# db9neogeo.net
KiCad netlist of a schematic drawn in EAGLE
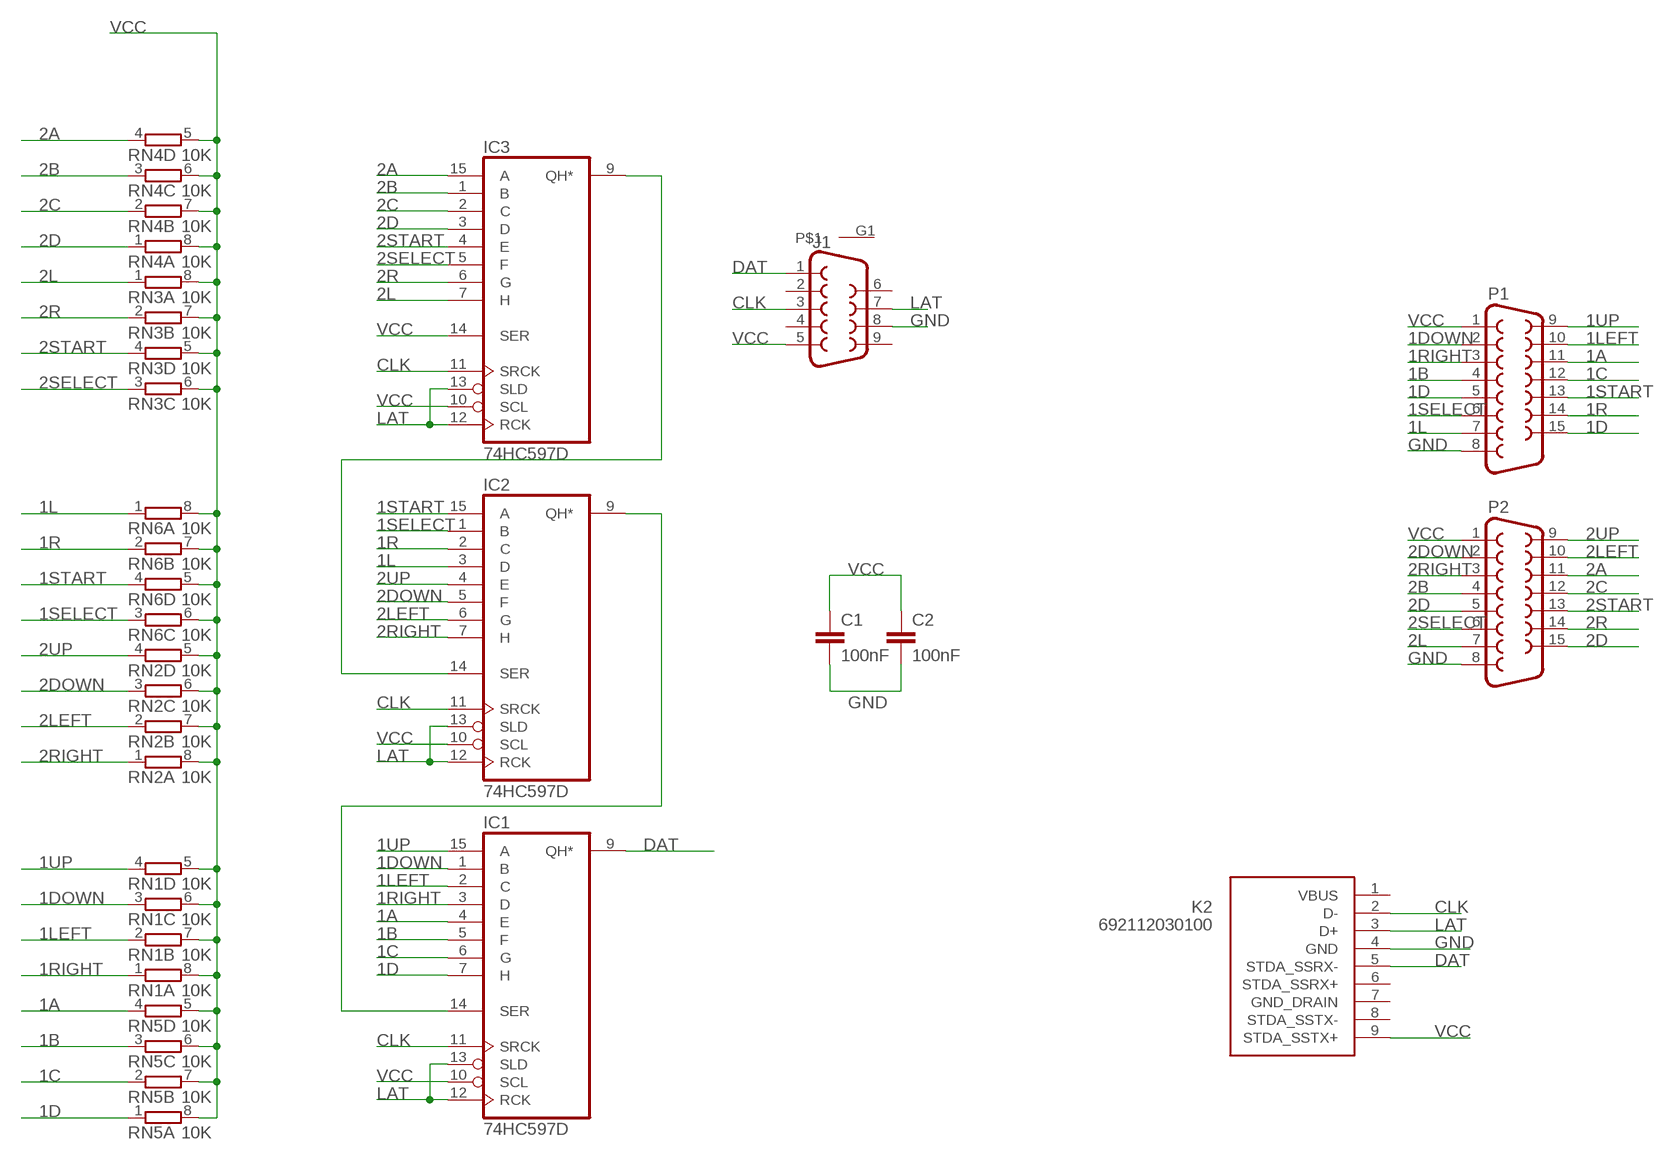
[diagram p0: schematic, sheet 1]

(export (version "E")
  (design (tool "Eeschema 10.0.6"))
  (components
    (comp (ref "C1")
      (value "100nF")
      (footprint "eagle-import:C0603K")
      (libsource (lib "eagle-import") (part "C-EUC0603K"))
    )
    (comp (ref "C2")
      (value "100nF")
      (footprint "eagle-import:C0603K")
      (libsource (lib "eagle-import") (part "C-EUC0603K"))
    )
    (comp (ref "IC1")
      (value "74HC597D")
      (footprint "eagle-import:SO16")
      (libsource (lib "eagle-import") (part "74597DHC"))
    )
    (comp (ref "IC2")
      (value "74HC597D")
      (footprint "eagle-import:SO16")
      (libsource (lib "eagle-import") (part "74597DHC"))
    )
    (comp (ref "IC3")
      (value "74HC597D")
      (footprint "eagle-import:SO16")
      (libsource (lib "eagle-import") (part "74597DHC"))
    )
    (comp (ref "J1")
      (value "DB9FEMALE")
      (footprint "eagle-import:DB9")
      (libsource (lib "eagle-import") (part "DB9FEMALE"))
    )
    (comp (ref "K2")
      (value "692112030100")
      (footprint "eagle-import:692112030100")
      (libsource (lib "eagle-import") (part "692112030100"))
    )
    (comp (ref "P1")
      (value "F15HP")
      (footprint "eagle-import:F15HP")
      (libsource (lib "eagle-import") (part "F15HP"))
    )
    (comp (ref "P2")
      (value "F15HP")
      (footprint "eagle-import:F15HP")
      (libsource (lib "eagle-import") (part "F15HP"))
    )
    (comp (ref "RN1")
      (value "10K")
      (footprint "eagle-import:0603-ARC")
      (libsource (lib "eagle-import") (part "4R-N0603-ARC"))
    )
    (comp (ref "RN2")
      (value "10K")
      (footprint "eagle-import:0603-ARC")
      (libsource (lib "eagle-import") (part "4R-N0603-ARC"))
    )
    (comp (ref "RN3")
      (value "10K")
      (footprint "eagle-import:0603-ARC")
      (libsource (lib "eagle-import") (part "4R-N0603-ARC"))
    )
    (comp (ref "RN4")
      (value "10K")
      (footprint "eagle-import:0603-ARC")
      (libsource (lib "eagle-import") (part "4R-N0603-ARC"))
    )
    (comp (ref "RN5")
      (value "10K")
      (footprint "eagle-import:0603-ARC")
      (libsource (lib "eagle-import") (part "4R-N0603-ARC"))
    )
    (comp (ref "RN6")
      (value "10K")
      (footprint "eagle-import:0603-ARC")
      (libsource (lib "eagle-import") (part "4R-N0603-ARC"))
    )
  )
  (nets
    (net (code "1") (name "/1A") (class "Default")
      (node (ref "IC1") (pin "4") (pinfunction "E_4") (pintype "input"))
      (node (ref "P1") (pin "11") (pinfunction "11_11") (pintype "passive"))
      (node (ref "RN5") (pin "4") (pinfunction "1_4") (pintype "passive"))
    )
    (net (code "2") (name "/1B") (class "Default")
      (node (ref "IC1") (pin "5") (pinfunction "F_5") (pintype "input"))
      (node (ref "P1") (pin "4") (pinfunction "4_4") (pintype "passive"))
      (node (ref "RN5") (pin "3") (pinfunction "1_3") (pintype "passive"))
    )
    (net (code "3") (name "/1C") (class "Default")
      (node (ref "IC1") (pin "6") (pinfunction "G_6") (pintype "input"))
      (node (ref "P1") (pin "12") (pinfunction "12_12") (pintype "passive"))
      (node (ref "RN5") (pin "2") (pinfunction "1_2") (pintype "passive"))
    )
    (net (code "4") (name "/1D") (class "Default")
      (node (ref "IC1") (pin "7") (pinfunction "H_7") (pintype "input"))
      (node (ref "P1") (pin "15") (pinfunction "15_15") (pintype "passive"))
      (node (ref "P1") (pin "5") (pinfunction "5_5") (pintype "passive"))
      (node (ref "RN5") (pin "1") (pinfunction "1_1") (pintype "passive"))
    )
    (net (code "5") (name "/1DOWN") (class "Default")
      (node (ref "IC1") (pin "1") (pinfunction "B_1") (pintype "input"))
      (node (ref "P1") (pin "2") (pinfunction "2_2") (pintype "passive"))
      (node (ref "RN1") (pin "3") (pinfunction "1_3") (pintype "passive"))
    )
    (net (code "6") (name "/1L") (class "Default")
      (node (ref "IC2") (pin "3") (pinfunction "D_3") (pintype "input"))
      (node (ref "P1") (pin "7") (pinfunction "7_7") (pintype "passive"))
      (node (ref "RN6") (pin "1") (pinfunction "1_1") (pintype "passive"))
    )
    (net (code "7") (name "/1LEFT") (class "Default")
      (node (ref "IC1") (pin "2") (pinfunction "C_2") (pintype "input"))
      (node (ref "P1") (pin "10") (pinfunction "10_10") (pintype "passive"))
      (node (ref "RN1") (pin "2") (pinfunction "1_2") (pintype "passive"))
    )
    (net (code "8") (name "/1R") (class "Default")
      (node (ref "IC2") (pin "2") (pinfunction "C_2") (pintype "input"))
      (node (ref "P1") (pin "14") (pinfunction "14_14") (pintype "passive"))
      (node (ref "RN6") (pin "2") (pinfunction "1_2") (pintype "passive"))
    )
    (net (code "9") (name "/1RIGHT") (class "Default")
      (node (ref "IC1") (pin "3") (pinfunction "D_3") (pintype "input"))
      (node (ref "P1") (pin "3") (pinfunction "3_3") (pintype "passive"))
      (node (ref "RN1") (pin "1") (pinfunction "1_1") (pintype "passive"))
    )
    (net (code "10") (name "/1SELECT") (class "Default")
      (node (ref "IC2") (pin "1") (pinfunction "B_1") (pintype "input"))
      (node (ref "P1") (pin "6") (pinfunction "6_6") (pintype "passive"))
      (node (ref "RN6") (pin "3") (pinfunction "1_3") (pintype "passive"))
    )
    (net (code "11") (name "/1START") (class "Default")
      (node (ref "IC2") (pin "15") (pinfunction "A_15") (pintype "input"))
      (node (ref "P1") (pin "13") (pinfunction "13_13") (pintype "passive"))
      (node (ref "RN6") (pin "4") (pinfunction "1_4") (pintype "passive"))
    )
    (net (code "12") (name "/1UP") (class "Default")
      (node (ref "IC1") (pin "15") (pinfunction "A_15") (pintype "input"))
      (node (ref "P1") (pin "9") (pinfunction "9_9") (pintype "passive"))
      (node (ref "RN1") (pin "4") (pinfunction "1_4") (pintype "passive"))
    )
    (net (code "13") (name "/2A") (class "Default")
      (node (ref "IC3") (pin "15") (pinfunction "A_15") (pintype "input"))
      (node (ref "P2") (pin "11") (pinfunction "11_11") (pintype "passive"))
      (node (ref "RN4") (pin "4") (pinfunction "1_4") (pintype "passive"))
    )
    (net (code "14") (name "/2B") (class "Default")
      (node (ref "IC3") (pin "1") (pinfunction "B_1") (pintype "input"))
      (node (ref "P2") (pin "4") (pinfunction "4_4") (pintype "passive"))
      (node (ref "RN4") (pin "3") (pinfunction "1_3") (pintype "passive"))
    )
    (net (code "15") (name "/2C") (class "Default")
      (node (ref "IC3") (pin "2") (pinfunction "C_2") (pintype "input"))
      (node (ref "P2") (pin "12") (pinfunction "12_12") (pintype "passive"))
      (node (ref "RN4") (pin "2") (pinfunction "1_2") (pintype "passive"))
    )
    (net (code "16") (name "/2D") (class "Default")
      (node (ref "IC3") (pin "3") (pinfunction "D_3") (pintype "input"))
      (node (ref "P2") (pin "15") (pinfunction "15_15") (pintype "passive"))
      (node (ref "P2") (pin "5") (pinfunction "5_5") (pintype "passive"))
      (node (ref "RN4") (pin "1") (pinfunction "1_1") (pintype "passive"))
    )
    (net (code "17") (name "/2DOWN") (class "Default")
      (node (ref "IC2") (pin "5") (pinfunction "F_5") (pintype "input"))
      (node (ref "P2") (pin "2") (pinfunction "2_2") (pintype "passive"))
      (node (ref "RN2") (pin "3") (pinfunction "1_3") (pintype "passive"))
    )
    (net (code "18") (name "/2L") (class "Default")
      (node (ref "IC3") (pin "7") (pinfunction "H_7") (pintype "input"))
      (node (ref "P2") (pin "7") (pinfunction "7_7") (pintype "passive"))
      (node (ref "RN3") (pin "1") (pinfunction "1_1") (pintype "passive"))
    )
    (net (code "19") (name "/2LEFT") (class "Default")
      (node (ref "IC2") (pin "6") (pinfunction "G_6") (pintype "input"))
      (node (ref "P2") (pin "10") (pinfunction "10_10") (pintype "passive"))
      (node (ref "RN2") (pin "2") (pinfunction "1_2") (pintype "passive"))
    )
    (net (code "20") (name "/2R") (class "Default")
      (node (ref "IC3") (pin "6") (pinfunction "G_6") (pintype "input"))
      (node (ref "P2") (pin "14") (pinfunction "14_14") (pintype "passive"))
      (node (ref "RN3") (pin "2") (pinfunction "1_2") (pintype "passive"))
    )
    (net (code "21") (name "/2RIGHT") (class "Default")
      (node (ref "IC2") (pin "7") (pinfunction "H_7") (pintype "input"))
      (node (ref "P2") (pin "3") (pinfunction "3_3") (pintype "passive"))
      (node (ref "RN2") (pin "1") (pinfunction "1_1") (pintype "passive"))
    )
    (net (code "22") (name "/2SELECT") (class "Default")
      (node (ref "IC3") (pin "5") (pinfunction "F_5") (pintype "input"))
      (node (ref "P2") (pin "6") (pinfunction "6_6") (pintype "passive"))
      (node (ref "RN3") (pin "3") (pinfunction "1_3") (pintype "passive"))
    )
    (net (code "23") (name "/2START") (class "Default")
      (node (ref "IC3") (pin "4") (pinfunction "E_4") (pintype "input"))
      (node (ref "P2") (pin "13") (pinfunction "13_13") (pintype "passive"))
      (node (ref "RN3") (pin "4") (pinfunction "1_4") (pintype "passive"))
    )
    (net (code "24") (name "/2UP") (class "Default")
      (node (ref "IC2") (pin "4") (pinfunction "E_4") (pintype "input"))
      (node (ref "P2") (pin "9") (pinfunction "9_9") (pintype "passive"))
      (node (ref "RN2") (pin "4") (pinfunction "1_4") (pintype "passive"))
    )
    (net (code "25") (name "/CLK") (class "Default")
      (node (ref "IC1") (pin "11") (pinfunction "SRCK_11") (pintype "input"))
      (node (ref "IC2") (pin "11") (pinfunction "SRCK_11") (pintype "input"))
      (node (ref "IC3") (pin "11") (pinfunction "SRCK_11") (pintype "input"))
      (node (ref "J1") (pin "3") (pinfunction "3_3") (pintype "passive"))
      (node (ref "K2") (pin "2") (pinfunction "D-_2") (pintype "bidirectional"))
    )
    (net (code "26") (name "/DAT") (class "Default")
      (node (ref "IC1") (pin "9") (pinfunction "QH*_9") (pintype "output"))
      (node (ref "J1") (pin "1") (pinfunction "1_1") (pintype "passive"))
      (node (ref "K2") (pin "5") (pinfunction "STDA_SSRX-_5") (pintype "bidirectional"))
    )
    (net (code "27") (name "/GND") (class "Default")
      (node (ref "C1") (pin "2") (pinfunction "2_2") (pintype "passive"))
      (node (ref "C2") (pin "2") (pinfunction "2_2") (pintype "passive"))
      (node (ref "J1") (pin "8") (pinfunction "8_8") (pintype "passive"))
      (node (ref "K2") (pin "4") (pinfunction "GND_4") (pintype "bidirectional"))
      (node (ref "P1") (pin "8") (pinfunction "8_8") (pintype "passive"))
      (node (ref "P2") (pin "8") (pinfunction "8_8") (pintype "passive"))
    )
    (net (code "28") (name "/LAT") (class "Default")
      (node (ref "IC1") (pin "12") (pinfunction "RCK_12") (pintype "input"))
      (node (ref "IC1") (pin "13") (pinfunction "SLD_13") (pintype "input"))
      (node (ref "IC2") (pin "12") (pinfunction "RCK_12") (pintype "input"))
      (node (ref "IC2") (pin "13") (pinfunction "SLD_13") (pintype "input"))
      (node (ref "IC3") (pin "12") (pinfunction "RCK_12") (pintype "input"))
      (node (ref "IC3") (pin "13") (pinfunction "SLD_13") (pintype "input"))
      (node (ref "J1") (pin "7") (pinfunction "7_7") (pintype "passive"))
      (node (ref "K2") (pin "3") (pinfunction "D+_3") (pintype "bidirectional"))
    )
    (net (code "29") (name "/VCC") (class "Default")
      (node (ref "C1") (pin "1") (pinfunction "1_1") (pintype "passive"))
      (node (ref "C2") (pin "1") (pinfunction "1_1") (pintype "passive"))
      (node (ref "IC1") (pin "10") (pinfunction "SCL_10") (pintype "input"))
      (node (ref "IC2") (pin "10") (pinfunction "SCL_10") (pintype "input"))
      (node (ref "IC3") (pin "10") (pinfunction "SCL_10") (pintype "input"))
      (node (ref "IC3") (pin "14") (pinfunction "SER_14") (pintype "input"))
      (node (ref "J1") (pin "5") (pinfunction "5_5") (pintype "passive"))
      (node (ref "K2") (pin "9") (pinfunction "STDA_SSTX+_9") (pintype "bidirectional"))
      (node (ref "P1") (pin "1") (pinfunction "1_1") (pintype "passive"))
      (node (ref "P2") (pin "1") (pinfunction "1_1") (pintype "passive"))
      (node (ref "RN1") (pin "5") (pinfunction "2_5") (pintype "passive"))
      (node (ref "RN1") (pin "6") (pinfunction "2_6") (pintype "passive"))
      (node (ref "RN1") (pin "7") (pinfunction "2_7") (pintype "passive"))
      (node (ref "RN1") (pin "8") (pinfunction "2_8") (pintype "passive"))
      (node (ref "RN2") (pin "5") (pinfunction "2_5") (pintype "passive"))
      (node (ref "RN2") (pin "6") (pinfunction "2_6") (pintype "passive"))
      (node (ref "RN2") (pin "7") (pinfunction "2_7") (pintype "passive"))
      (node (ref "RN2") (pin "8") (pinfunction "2_8") (pintype "passive"))
      (node (ref "RN3") (pin "5") (pinfunction "2_5") (pintype "passive"))
      (node (ref "RN3") (pin "6") (pinfunction "2_6") (pintype "passive"))
      (node (ref "RN3") (pin "7") (pinfunction "2_7") (pintype "passive"))
      (node (ref "RN3") (pin "8") (pinfunction "2_8") (pintype "passive"))
      (node (ref "RN4") (pin "5") (pinfunction "2_5") (pintype "passive"))
      (node (ref "RN4") (pin "6") (pinfunction "2_6") (pintype "passive"))
      (node (ref "RN4") (pin "7") (pinfunction "2_7") (pintype "passive"))
      (node (ref "RN4") (pin "8") (pinfunction "2_8") (pintype "passive"))
      (node (ref "RN5") (pin "5") (pinfunction "2_5") (pintype "passive"))
      (node (ref "RN5") (pin "6") (pinfunction "2_6") (pintype "passive"))
      (node (ref "RN5") (pin "7") (pinfunction "2_7") (pintype "passive"))
      (node (ref "RN5") (pin "8") (pinfunction "2_8") (pintype "passive"))
      (node (ref "RN6") (pin "5") (pinfunction "2_5") (pintype "passive"))
      (node (ref "RN6") (pin "6") (pinfunction "2_6") (pintype "passive"))
      (node (ref "RN6") (pin "7") (pinfunction "2_7") (pintype "passive"))
      (node (ref "RN6") (pin "8") (pinfunction "2_8") (pintype "passive"))
    )
    (net (code "30") (name "Net-(IC1A-SER)") (class "Default")
      (node (ref "IC1") (pin "14") (pinfunction "SER_14") (pintype "input"))
      (node (ref "IC2") (pin "9") (pinfunction "QH*_9") (pintype "output"))
    )
    (net (code "31") (name "Net-(IC2A-SER)") (class "Default")
      (node (ref "IC2") (pin "14") (pinfunction "SER_14") (pintype "input"))
      (node (ref "IC3") (pin "9") (pinfunction "QH*_9") (pintype "output"))
    )
    (net (code "32") (name "unconnected-(J1-P$1-PadG1)") (class "Default")
      (node (ref "J1") (pin "G1") (pinfunction "P$1_G1") (pintype "bidirectional"))
    )
    (net (code "33") (name "unconnected-(J1-Pad2)") (class "Default")
      (node (ref "J1") (pin "2") (pinfunction "2_2") (pintype "passive"))
    )
    (net (code "34") (name "unconnected-(J1-Pad4)") (class "Default")
      (node (ref "J1") (pin "4") (pinfunction "4_4") (pintype "passive"))
    )
    (net (code "35") (name "unconnected-(J1-Pad6)") (class "Default")
      (node (ref "J1") (pin "6") (pinfunction "6_6") (pintype "passive"))
    )
    (net (code "36") (name "unconnected-(J1-Pad9)") (class "Default")
      (node (ref "J1") (pin "9") (pinfunction "9_9") (pintype "passive"))
    )
    (net (code "37") (name "unconnected-(K2-GND_DRAIN-Pad7)") (class "Default")
      (node (ref "K2") (pin "7") (pinfunction "GND_DRAIN_7") (pintype "bidirectional"))
    )
    (net (code "38") (name "unconnected-(K2-STDA_SSRX+-Pad6)") (class "Default")
      (node (ref "K2") (pin "6") (pinfunction "STDA_SSRX+_6") (pintype "bidirectional"))
    )
    (net (code "39") (name "unconnected-(K2-STDA_SSTX--Pad8)") (class "Default")
      (node (ref "K2") (pin "8") (pinfunction "STDA_SSTX-_8") (pintype "bidirectional"))
    )
    (net (code "40") (name "unconnected-(K2-VBUS-Pad1)") (class "Default")
      (node (ref "K2") (pin "1") (pinfunction "VBUS_1") (pintype "bidirectional"))
    )
  )
)
